# Emergency_Light_with_Battery_Charger.net
KiCad netlist of a schematic drawn in EAGLE
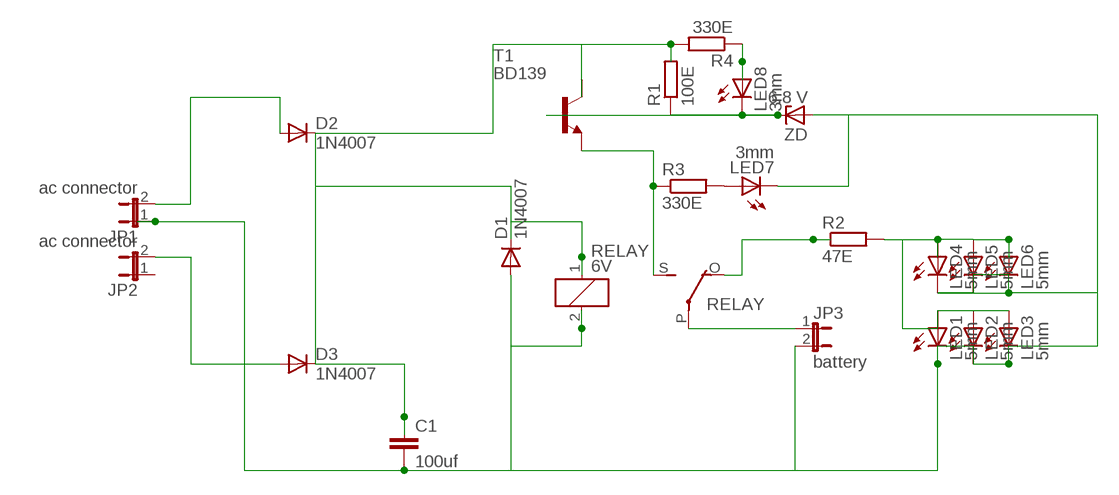
[diagram p0: schematic, sheet 1]

(export (version "E")
  (design (tool "Eeschema 10.0.6"))
  (components
    (comp (ref "C1")
      (value "100uf")
      (footprint "eagle-import:C2.5-5")
      (libsource (lib "eagle-import") (part "C2.5/5"))
    )
    (comp (ref "D1")
      (value "1N4007")
      (footprint "eagle-import:DO41-10")
      (libsource (lib "eagle-import") (part "1N4004"))
    )
    (comp (ref "D2")
      (value "1N4007")
      (footprint "eagle-import:DO41-10")
      (libsource (lib "eagle-import") (part "1N4004"))
    )
    (comp (ref "D3")
      (value "1N4007")
      (footprint "eagle-import:DO41-10")
      (libsource (lib "eagle-import") (part "1N4004"))
    )
    (comp (ref "JP1")
      (value "ac connector")
      (footprint "eagle-import:JP1")
      (libsource (lib "eagle-import") (part "JP1E"))
    )
    (comp (ref "JP2")
      (value "ac connector")
      (footprint "eagle-import:JP1")
      (libsource (lib "eagle-import") (part "JP1E"))
    )
    (comp (ref "JP3")
      (value "battery")
      (footprint "eagle-import:JP1")
      (libsource (lib "eagle-import") (part "JP1E"))
    )
    (comp (ref "LED1")
      (value "5mm")
      (footprint "eagle-import:LED5MM")
      (libsource (lib "eagle-import") (part "LED5MM"))
    )
    (comp (ref "LED2")
      (value "5mm")
      (footprint "eagle-import:LED5MM")
      (libsource (lib "eagle-import") (part "LED5MM"))
    )
    (comp (ref "LED3")
      (value "5mm")
      (footprint "eagle-import:LED5MM")
      (libsource (lib "eagle-import") (part "LED5MM"))
    )
    (comp (ref "LED4")
      (value "5mm")
      (footprint "eagle-import:LED5MM")
      (libsource (lib "eagle-import") (part "LED5MM"))
    )
    (comp (ref "LED5")
      (value "5mm")
      (footprint "eagle-import:LED5MM")
      (libsource (lib "eagle-import") (part "LED5MM"))
    )
    (comp (ref "LED6")
      (value "5mm")
      (footprint "eagle-import:LED5MM")
      (libsource (lib "eagle-import") (part "LED5MM"))
    )
    (comp (ref "LED7")
      (value "3mm")
      (footprint "eagle-import:LED3MM")
      (libsource (lib "eagle-import") (part "LED3MM"))
    )
    (comp (ref "LED8")
      (value "3mm")
      (footprint "eagle-import:LED3MM")
      (libsource (lib "eagle-import") (part "LED3MM"))
    )
    (comp (ref "R1")
      (value "100E")
      (footprint "eagle-import:0204_7")
      (libsource (lib "eagle-import") (part "R-EU_0204/7"))
    )
    (comp (ref "R2")
      (value "47E")
      (footprint "eagle-import:0204_7")
      (libsource (lib "eagle-import") (part "R-EU_0204/7"))
    )
    (comp (ref "R3")
      (value "330E")
      (footprint "eagle-import:0204_7")
      (libsource (lib "eagle-import") (part "R-EU_0204/7"))
    )
    (comp (ref "R4")
      (value "330E")
      (footprint "eagle-import:0204_7")
      (libsource (lib "eagle-import") (part "R-EU_0204/7"))
    )
    (comp (ref "RELAY")
      (value "6V")
      (footprint "eagle-import:G5LE")
      (libsource (lib "eagle-import") (part "G5L"))
    )
    (comp (ref "T1")
      (value "BD139")
      (footprint "eagle-import:TO126")
      (libsource (lib "eagle-import") (part "BD139"))
    )
    (comp (ref "ZD")
      (value "6.8 V")
      (footprint "eagle-import:DO35Z10")
      (libsource (lib "eagle-import") (part "ZPD"))
    )
  )
  (nets
    (net (code "1") (name "Net-(D2-PadA)") (class "Default")
      (node (ref "D2") (pin "A") (pinfunction "A_A") (pintype "passive"))
      (node (ref "JP1") (pin "2") (pinfunction "2_2") (pintype "passive"))
    )
    (net (code "2") (name "Net-(D3-PadA)") (class "Default")
      (node (ref "D3") (pin "A") (pinfunction "A_A") (pintype "passive"))
      (node (ref "JP2") (pin "2") (pinfunction "2_2") (pintype "passive"))
    )
    (net (code "3") (name "Net-(JP3-Pad1)") (class "Default")
      (node (ref "JP3") (pin "1") (pinfunction "1_1") (pintype "passive"))
      (node (ref "RELAY") (pin "P") (pinfunction "P_P") (pintype "passive"))
    )
    (net (code "4") (name "Net-(LED1-C)") (class "Default")
      (node (ref "C1") (pin "2") (pinfunction "2_2") (pintype "passive"))
      (node (ref "D1") (pin "A") (pinfunction "A_A") (pintype "passive"))
      (node (ref "JP1") (pin "1") (pinfunction "1_1") (pintype "passive"))
      (node (ref "JP3") (pin "2") (pinfunction "2_2") (pintype "passive"))
      (node (ref "LED1") (pin "K") (pinfunction "C_K") (pintype "passive"))
      (node (ref "LED2") (pin "K") (pinfunction "C_K") (pintype "passive"))
      (node (ref "LED3") (pin "K") (pinfunction "C_K") (pintype "passive"))
      (node (ref "LED4") (pin "K") (pinfunction "C_K") (pintype "passive"))
      (node (ref "LED5") (pin "K") (pinfunction "C_K") (pintype "passive"))
      (node (ref "LED6") (pin "K") (pinfunction "C_K") (pintype "passive"))
      (node (ref "LED7") (pin "K") (pinfunction "C_K") (pintype "passive"))
      (node (ref "RELAY") (pin "2") (pinfunction "2_2") (pintype "passive"))
      (node (ref "ZD") (pin "A") (pinfunction "A_A") (pintype "passive"))
    )
    (net (code "5") (name "Net-(LED1-PadA)") (class "Default")
      (node (ref "LED1") (pin "A") (pinfunction "A_A") (pintype "passive"))
      (node (ref "LED2") (pin "A") (pinfunction "A_A") (pintype "passive"))
      (node (ref "LED3") (pin "A") (pinfunction "A_A") (pintype "passive"))
      (node (ref "LED4") (pin "A") (pinfunction "A_A") (pintype "passive"))
      (node (ref "LED5") (pin "A") (pinfunction "A_A") (pintype "passive"))
      (node (ref "LED6") (pin "A") (pinfunction "A_A") (pintype "passive"))
      (node (ref "R2") (pin "2") (pinfunction "2_2") (pintype "passive"))
    )
    (net (code "6") (name "Net-(LED7-PadA)") (class "Default")
      (node (ref "LED7") (pin "A") (pinfunction "A_A") (pintype "passive"))
      (node (ref "R3") (pin "2") (pinfunction "2_2") (pintype "passive"))
    )
    (net (code "7") (name "Net-(LED8-C)") (class "Default")
      (node (ref "LED8") (pin "K") (pinfunction "C_K") (pintype "passive"))
      (node (ref "R1") (pin "1") (pinfunction "1_1") (pintype "passive"))
      (node (ref "T1") (pin "3") (pinfunction "B_3") (pintype "passive"))
      (node (ref "ZD") (pin "C") (pinfunction "C_C") (pintype "passive"))
    )
    (net (code "8") (name "Net-(LED8-PadA)") (class "Default")
      (node (ref "LED8") (pin "A") (pinfunction "A_A") (pintype "passive"))
      (node (ref "R4") (pin "1") (pinfunction "1_1") (pintype "passive"))
    )
    (net (code "9") (name "Net-(R2-Pad1)") (class "Default")
      (node (ref "R2") (pin "1") (pinfunction "1_1") (pintype "passive"))
      (node (ref "RELAY") (pin "O") (pinfunction "O_O") (pintype "passive"))
    )
    (net (code "10") (name "Net-(T1-C)") (class "Default")
      (node (ref "C1") (pin "1") (pinfunction "1_1") (pintype "passive"))
      (node (ref "D1") (pin "C") (pinfunction "C_C") (pintype "passive"))
      (node (ref "D2") (pin "C") (pinfunction "C_C") (pintype "passive"))
      (node (ref "D3") (pin "C") (pinfunction "C_C") (pintype "passive"))
      (node (ref "R1") (pin "2") (pinfunction "2_2") (pintype "passive"))
      (node (ref "R4") (pin "2") (pinfunction "2_2") (pintype "passive"))
      (node (ref "RELAY") (pin "1") (pinfunction "1_1") (pintype "passive"))
      (node (ref "T1") (pin "2") (pinfunction "C_2") (pintype "passive"))
    )
    (net (code "11") (name "Net-(T1-E)") (class "Default")
      (node (ref "R3") (pin "1") (pinfunction "1_1") (pintype "passive"))
      (node (ref "RELAY") (pin "S") (pinfunction "S_S") (pintype "passive"))
      (node (ref "T1") (pin "1") (pinfunction "E_1") (pintype "passive"))
    )
    (net (code "12") (name "unconnected-(JP2-Pad1)") (class "Default")
      (node (ref "JP2") (pin "1") (pinfunction "1_1") (pintype "passive"))
    )
  )
)
